# bh_ai8_di8_alph_back.net
KiCad netlist of a schematic drawn in Altium Designer
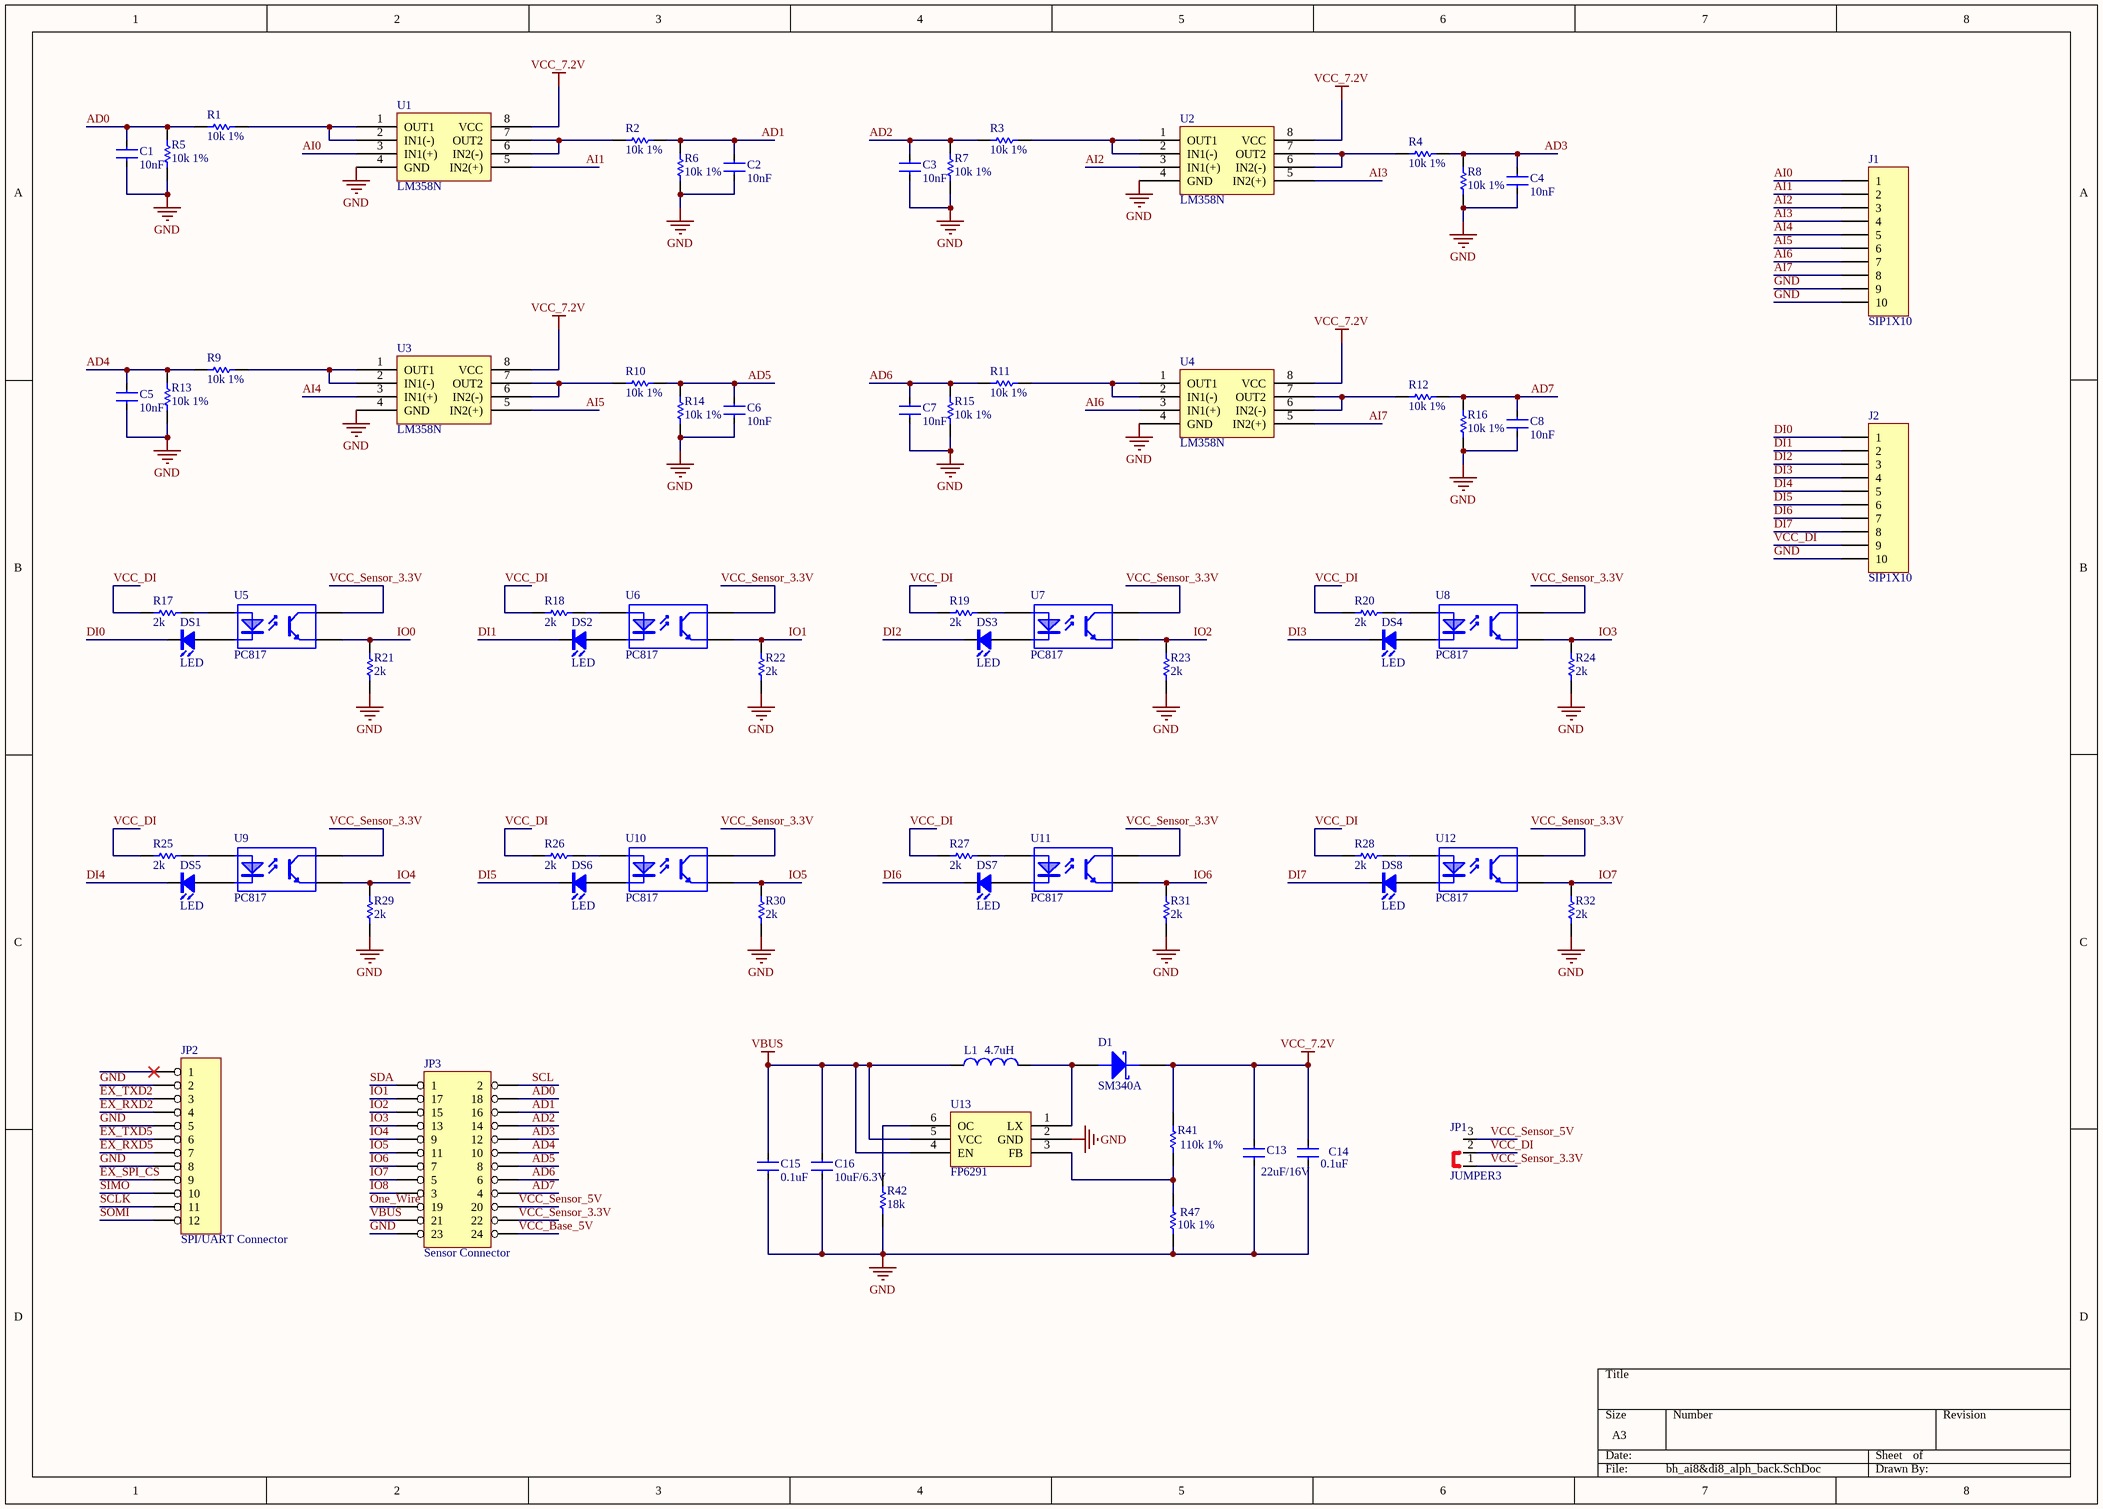
[diagram p0: bh_ai8&di8_alph_back.SchDoc]

(export (version "E")
  (design (tool "Eeschema 10.0.6"))
  (components
    (comp (ref "C1")
      (value "10nF")
      (footprint "C0603")
      (description "SMD-CAP")
      (fields (field (name "Comment") "CAP-SMD"))
      (libsource (lib "BH_DESIGN_DEVICE") (part "CAP-SMD"))
    )
    (comp (ref "C2")
      (value "10nF")
      (footprint "C0603")
      (description "SMD-CAP")
      (fields (field (name "Comment") "CAP-SMD"))
      (libsource (lib "BH_DESIGN_DEVICE") (part "CAP-SMD"))
    )
    (comp (ref "C3")
      (value "10nF")
      (footprint "C0603")
      (description "SMD-CAP")
      (fields (field (name "Comment") "CAP-SMD"))
      (libsource (lib "BH_DESIGN_DEVICE") (part "CAP-SMD"))
    )
    (comp (ref "C4")
      (value "10nF")
      (footprint "C0603")
      (description "SMD-CAP")
      (fields (field (name "Comment") "CAP-SMD"))
      (libsource (lib "BH_DESIGN_DEVICE") (part "CAP-SMD"))
    )
    (comp (ref "C5")
      (value "10nF")
      (footprint "C0603")
      (description "SMD-CAP")
      (fields (field (name "Comment") "CAP-SMD"))
      (libsource (lib "BH_DESIGN_DEVICE") (part "CAP-SMD"))
    )
    (comp (ref "C6")
      (value "10nF")
      (footprint "C0603")
      (description "SMD-CAP")
      (fields (field (name "Comment") "CAP-SMD"))
      (libsource (lib "BH_DESIGN_DEVICE") (part "CAP-SMD"))
    )
    (comp (ref "C7")
      (value "10nF")
      (footprint "C0603")
      (description "SMD-CAP")
      (fields (field (name "Comment") "CAP-SMD"))
      (libsource (lib "BH_DESIGN_DEVICE") (part "CAP-SMD"))
    )
    (comp (ref "C8")
      (value "10nF")
      (footprint "C0603")
      (description "SMD-CAP")
      (fields (field (name "Comment") "CAP-SMD"))
      (libsource (lib "BH_DESIGN_DEVICE") (part "CAP-SMD"))
    )
    (comp (ref "C13")
      (value "22uF/16V")
      (footprint "C0805")
      (description "SMD-CAP")
      (libsource (lib "5D_DEVICE") (part "CAP-SMD"))
    )
    (comp (ref "C14")
      (value "0.1uF")
      (footprint "C0603")
      (description "SMD-CAP")
      (libsource (lib "5D_DEVICE") (part "CAP-SMD"))
    )
    (comp (ref "C15")
      (value "0.1uF")
      (footprint "C0603")
      (description "SMD-CAP")
      (libsource (lib "5D_DEVICE") (part "CAP-SMD"))
    )
    (comp (ref "C16")
      (value "10uF/6.3V")
      (footprint "C0805")
      (description "SMD-CAP")
      (libsource (lib "5D_DEVICE") (part "CAP-SMD"))
    )
    (comp (ref "D1")
      (value "SM340A")
      (footprint "DO-214")
      (description "Schottky Diode")
      (libsource (lib "5D_DEVICE") (part "DIODE SCHOTTKY"))
    )
    (comp (ref "DS1") (value "LED") (footprint "D0805") (libsource (lib "BH_DESIGN_DEVICE") (part "LED")))
    (comp (ref "DS2") (value "LED") (footprint "D0805") (libsource (lib "BH_DESIGN_DEVICE") (part "LED")))
    (comp (ref "DS3") (value "LED") (footprint "D0805") (libsource (lib "BH_DESIGN_DEVICE") (part "LED")))
    (comp (ref "DS4") (value "LED") (footprint "D0805") (libsource (lib "BH_DESIGN_DEVICE") (part "LED")))
    (comp (ref "DS5") (value "LED") (footprint "D0805") (libsource (lib "BH_DESIGN_DEVICE") (part "LED")))
    (comp (ref "DS6") (value "LED") (footprint "D0805") (libsource (lib "BH_DESIGN_DEVICE") (part "LED")))
    (comp (ref "DS7") (value "LED") (footprint "D0805") (libsource (lib "BH_DESIGN_DEVICE") (part "LED")))
    (comp (ref "DS8") (value "LED") (footprint "D0805") (libsource (lib "BH_DESIGN_DEVICE") (part "LED")))
    (comp (ref "J1")
      (value "SIP1X10")
      (footprint "CON10*0.381")
      (description "Connector")
      (libsource (lib "BH_DESIGN_CONNECTOR") (part "SIP1X10"))
    )
    (comp (ref "J2")
      (value "SIP1X10")
      (footprint "CON10*0.381")
      (description "Connector")
      (libsource (lib "BH_DESIGN_CONNECTOR") (part "SIP1X10"))
    )
    (comp (ref "JP1")
      (value "JUMPER3")
      (footprint "SIP1X3X2.54")
      (description "Jumper")
      (libsource (lib "BH_DESIGN_CONNECTOR") (part "JUMPER3"))
    )
    (comp (ref "JP2")
      (value "SPI/UART Connector")
      (footprint "SIP1x12x2.54")
      (description "12 Pin Header")
      (libsource (lib "5D_CONNECTOR") (part "SIP1X12"))
    )
    (comp (ref "JP3")
      (value "Sensor Connector")
      (footprint "SIP2X12X2.54")
      (libsource (lib "5D_CONNECTOR") (part "SIP2X12"))
    )
    (comp (ref "L1")
      (value "4.7uH")
      (footprint "R1206")
      (description "Inductor")
      (fields (field (name "Comment") "INDUCTOR"))
      (libsource (lib "5D_DEVICE") (part "INDUCTOR"))
    )
    (comp (ref "R1")
      (value "10k 1%")
      (footprint "R0603")
      (description "Resistor")
      (libsource (lib "BH_DESIGN_DEVICE") (part "RES"))
    )
    (comp (ref "R2")
      (value "10k 1%")
      (footprint "R0603")
      (description "Resistor")
      (libsource (lib "BH_DESIGN_DEVICE") (part "RES"))
    )
    (comp (ref "R3")
      (value "10k 1%")
      (footprint "R0603")
      (description "Resistor")
      (libsource (lib "BH_DESIGN_DEVICE") (part "RES"))
    )
    (comp (ref "R4")
      (value "10k 1%")
      (footprint "R0603")
      (description "Resistor")
      (libsource (lib "BH_DESIGN_DEVICE") (part "RES"))
    )
    (comp (ref "R5")
      (value "10k 1%")
      (footprint "R0603")
      (description "Resistor")
      (libsource (lib "BH_DESIGN_DEVICE") (part "RES"))
    )
    (comp (ref "R6")
      (value "10k 1%")
      (footprint "R0603")
      (description "Resistor")
      (libsource (lib "BH_DESIGN_DEVICE") (part "RES"))
    )
    (comp (ref "R7")
      (value "10k 1%")
      (footprint "R0603")
      (description "Resistor")
      (libsource (lib "BH_DESIGN_DEVICE") (part "RES"))
    )
    (comp (ref "R8")
      (value "10k 1%")
      (footprint "R0603")
      (description "Resistor")
      (libsource (lib "BH_DESIGN_DEVICE") (part "RES"))
    )
    (comp (ref "R9")
      (value "10k 1%")
      (footprint "R0603")
      (description "Resistor")
      (libsource (lib "BH_DESIGN_DEVICE") (part "RES"))
    )
    (comp (ref "R10")
      (value "10k 1%")
      (footprint "R0603")
      (description "Resistor")
      (libsource (lib "BH_DESIGN_DEVICE") (part "RES"))
    )
    (comp (ref "R11")
      (value "10k 1%")
      (footprint "R0603")
      (description "Resistor")
      (libsource (lib "BH_DESIGN_DEVICE") (part "RES"))
    )
    (comp (ref "R12")
      (value "10k 1%")
      (footprint "R0603")
      (description "Resistor")
      (libsource (lib "BH_DESIGN_DEVICE") (part "RES"))
    )
    (comp (ref "R13")
      (value "10k 1%")
      (footprint "R0603")
      (description "Resistor")
      (libsource (lib "BH_DESIGN_DEVICE") (part "RES"))
    )
    (comp (ref "R14")
      (value "10k 1%")
      (footprint "R0603")
      (description "Resistor")
      (libsource (lib "BH_DESIGN_DEVICE") (part "RES"))
    )
    (comp (ref "R15")
      (value "10k 1%")
      (footprint "R0603")
      (description "Resistor")
      (libsource (lib "BH_DESIGN_DEVICE") (part "RES"))
    )
    (comp (ref "R16")
      (value "10k 1%")
      (footprint "R0603")
      (description "Resistor")
      (libsource (lib "BH_DESIGN_DEVICE") (part "RES"))
    )
    (comp (ref "R17")
      (value "2k")
      (footprint "R0603")
      (description "Resistor")
      (libsource (lib "BH_DESIGN_DEVICE") (part "RES"))
    )
    (comp (ref "R18")
      (value "2k")
      (footprint "R0603")
      (description "Resistor")
      (libsource (lib "BH_DESIGN_DEVICE") (part "RES"))
    )
    (comp (ref "R19")
      (value "2k")
      (footprint "R0603")
      (description "Resistor")
      (libsource (lib "BH_DESIGN_DEVICE") (part "RES"))
    )
    (comp (ref "R20")
      (value "2k")
      (footprint "R0603")
      (description "Resistor")
      (libsource (lib "BH_DESIGN_DEVICE") (part "RES"))
    )
    (comp (ref "R21")
      (value "2k")
      (footprint "R0603")
      (description "Resistor")
      (libsource (lib "BH_DESIGN_DEVICE") (part "RES"))
    )
    (comp (ref "R22")
      (value "2k")
      (footprint "R0603")
      (description "Resistor")
      (libsource (lib "BH_DESIGN_DEVICE") (part "RES"))
    )
    (comp (ref "R23")
      (value "2k")
      (footprint "R0603")
      (description "Resistor")
      (libsource (lib "BH_DESIGN_DEVICE") (part "RES"))
    )
    (comp (ref "R24")
      (value "2k")
      (footprint "R0603")
      (description "Resistor")
      (libsource (lib "BH_DESIGN_DEVICE") (part "RES"))
    )
    (comp (ref "R25")
      (value "2k")
      (footprint "R0603")
      (description "Resistor")
      (libsource (lib "BH_DESIGN_DEVICE") (part "RES"))
    )
    (comp (ref "R26")
      (value "2k")
      (footprint "R0603")
      (description "Resistor")
      (libsource (lib "BH_DESIGN_DEVICE") (part "RES"))
    )
    (comp (ref "R27")
      (value "2k")
      (footprint "R0603")
      (description "Resistor")
      (libsource (lib "BH_DESIGN_DEVICE") (part "RES"))
    )
    (comp (ref "R28")
      (value "2k")
      (footprint "R0603")
      (description "Resistor")
      (libsource (lib "BH_DESIGN_DEVICE") (part "RES"))
    )
    (comp (ref "R29")
      (value "2k")
      (footprint "R0603")
      (description "Resistor")
      (libsource (lib "BH_DESIGN_DEVICE") (part "RES"))
    )
    (comp (ref "R30")
      (value "2k")
      (footprint "R0603")
      (description "Resistor")
      (libsource (lib "BH_DESIGN_DEVICE") (part "RES"))
    )
    (comp (ref "R31")
      (value "2k")
      (footprint "R0603")
      (description "Resistor")
      (libsource (lib "BH_DESIGN_DEVICE") (part "RES"))
    )
    (comp (ref "R32")
      (value "2k")
      (footprint "R0603")
      (description "Resistor")
      (libsource (lib "BH_DESIGN_DEVICE") (part "RES"))
    )
    (comp (ref "R41")
      (value "110k 1%")
      (footprint "R0603")
      (description "Resistor")
      (libsource (lib "5D_DEVICE") (part "RES"))
    )
    (comp (ref "R42")
      (value "18k")
      (footprint "R0603")
      (description "Resistor")
      (libsource (lib "5D_DEVICE") (part "RES"))
    )
    (comp (ref "R47")
      (value "10k 1%")
      (footprint "R0603")
      (description "Resistor")
      (libsource (lib "5D_DEVICE") (part "RES"))
    )
    (comp (ref "U1") (value "LM358N") (footprint "SO8NB") (libsource (lib "BH_DESIGN_IC") (part "LM358N")))
    (comp (ref "U2") (value "LM358N") (footprint "SO8NB") (libsource (lib "BH_DESIGN_IC") (part "LM358N")))
    (comp (ref "U3") (value "LM358N") (footprint "SO8NB") (libsource (lib "BH_DESIGN_IC") (part "LM358N")))
    (comp (ref "U4") (value "LM358N") (footprint "SO8NB") (libsource (lib "BH_DESIGN_IC") (part "LM358N")))
    (comp (ref "U5")
      (value "PC817")
      (footprint "SOP_4")
      (fields (field (name "PUBLISHER") "Altium Limited"))
      (libsource (lib "BH_DESIGN_DEVICE") (part "P521*1"))
    )
    (comp (ref "U6")
      (value "PC817")
      (footprint "SOP_4")
      (fields (field (name "PUBLISHER") "Altium Limited"))
      (libsource (lib "BH_DESIGN_DEVICE") (part "P521*1"))
    )
    (comp (ref "U7")
      (value "PC817")
      (footprint "SOP_4")
      (fields (field (name "PUBLISHER") "Altium Limited"))
      (libsource (lib "BH_DESIGN_DEVICE") (part "P521*1"))
    )
    (comp (ref "U8")
      (value "PC817")
      (footprint "SOP_4")
      (fields (field (name "PUBLISHER") "Altium Limited"))
      (libsource (lib "BH_DESIGN_DEVICE") (part "P521*1"))
    )
    (comp (ref "U9")
      (value "PC817")
      (footprint "SOP_4")
      (fields (field (name "PUBLISHER") "Altium Limited"))
      (libsource (lib "BH_DESIGN_DEVICE") (part "P521*1"))
    )
    (comp (ref "U10")
      (value "PC817")
      (footprint "SOP_4")
      (fields (field (name "PUBLISHER") "Altium Limited"))
      (libsource (lib "BH_DESIGN_DEVICE") (part "P521*1"))
    )
    (comp (ref "U11")
      (value "PC817")
      (footprint "SOP_4")
      (fields (field (name "PUBLISHER") "Altium Limited"))
      (libsource (lib "BH_DESIGN_DEVICE") (part "P521*1"))
    )
    (comp (ref "U12")
      (value "PC817")
      (footprint "SOP_4")
      (fields (field (name "PUBLISHER") "Altium Limited"))
      (libsource (lib "BH_DESIGN_DEVICE") (part "P521*1"))
    )
    (comp (ref "U13") (value "FP6291") (footprint "SOT23-6") (libsource (lib "5D_IC") (part "FP6291")))
  )
  (nets
    (net (code "1") (name "/AD0") (class "Default")
      (node (ref "C1") (pin "1") (pinfunction "1_1") (pintype "passive"))
      (node (ref "JP3") (pin "18") (pinfunction "18_18") (pintype "passive"))
      (node (ref "R1") (pin "2") (pinfunction "2_2") (pintype "passive"))
      (node (ref "R5") (pin "1") (pinfunction "1_1") (pintype "passive"))
    )
    (net (code "2") (name "/AD1") (class "Default")
      (node (ref "C2") (pin "1") (pinfunction "1_1") (pintype "passive"))
      (node (ref "JP3") (pin "16") (pinfunction "16_16") (pintype "passive"))
      (node (ref "R2") (pin "1") (pinfunction "1_1") (pintype "passive"))
      (node (ref "R6") (pin "1") (pinfunction "1_1") (pintype "passive"))
    )
    (net (code "3") (name "/AD2") (class "Default")
      (node (ref "C3") (pin "1") (pinfunction "1_1") (pintype "passive"))
      (node (ref "JP3") (pin "14") (pinfunction "14_14") (pintype "passive"))
      (node (ref "R3") (pin "2") (pinfunction "2_2") (pintype "passive"))
      (node (ref "R7") (pin "1") (pinfunction "1_1") (pintype "passive"))
    )
    (net (code "4") (name "/AD3") (class "Default")
      (node (ref "C4") (pin "1") (pinfunction "1_1") (pintype "passive"))
      (node (ref "JP3") (pin "12") (pinfunction "12_12") (pintype "passive"))
      (node (ref "R4") (pin "1") (pinfunction "1_1") (pintype "passive"))
      (node (ref "R8") (pin "1") (pinfunction "1_1") (pintype "passive"))
    )
    (net (code "5") (name "/AD4") (class "Default")
      (node (ref "C5") (pin "1") (pinfunction "1_1") (pintype "passive"))
      (node (ref "JP3") (pin "10") (pinfunction "10_10") (pintype "passive"))
      (node (ref "R13") (pin "1") (pinfunction "1_1") (pintype "passive"))
      (node (ref "R9") (pin "2") (pinfunction "2_2") (pintype "passive"))
    )
    (net (code "6") (name "/AD5") (class "Default")
      (node (ref "C6") (pin "1") (pinfunction "1_1") (pintype "passive"))
      (node (ref "JP3") (pin "8") (pinfunction "8_8") (pintype "passive"))
      (node (ref "R10") (pin "1") (pinfunction "1_1") (pintype "passive"))
      (node (ref "R14") (pin "1") (pinfunction "1_1") (pintype "passive"))
    )
    (net (code "7") (name "/AD6") (class "Default")
      (node (ref "C7") (pin "1") (pinfunction "1_1") (pintype "passive"))
      (node (ref "JP3") (pin "6") (pinfunction "6_6") (pintype "passive"))
      (node (ref "R11") (pin "2") (pinfunction "2_2") (pintype "passive"))
      (node (ref "R15") (pin "1") (pinfunction "1_1") (pintype "passive"))
    )
    (net (code "8") (name "/AD7") (class "Default")
      (node (ref "C8") (pin "1") (pinfunction "1_1") (pintype "passive"))
      (node (ref "JP3") (pin "4") (pinfunction "4_4") (pintype "passive"))
      (node (ref "R12") (pin "1") (pinfunction "1_1") (pintype "passive"))
      (node (ref "R16") (pin "1") (pinfunction "1_1") (pintype "passive"))
    )
    (net (code "9") (name "/AI0") (class "Default")
      (node (ref "J1") (pin "1") (pinfunction "1_1") (pintype "passive"))
      (node (ref "U1") (pin "3") (pinfunction "IN1(+)_3") (pintype "passive"))
    )
    (net (code "10") (name "/AI1") (class "Default")
      (node (ref "J1") (pin "2") (pinfunction "2_2") (pintype "passive"))
      (node (ref "U1") (pin "5") (pinfunction "IN2(+)_5") (pintype "passive"))
    )
    (net (code "11") (name "/AI2") (class "Default")
      (node (ref "J1") (pin "3") (pinfunction "3_3") (pintype "passive"))
      (node (ref "U2") (pin "3") (pinfunction "IN1(+)_3") (pintype "passive"))
    )
    (net (code "12") (name "/AI3") (class "Default")
      (node (ref "J1") (pin "4") (pinfunction "4_4") (pintype "passive"))
      (node (ref "U2") (pin "5") (pinfunction "IN2(+)_5") (pintype "passive"))
    )
    (net (code "13") (name "/AI4") (class "Default")
      (node (ref "J1") (pin "5") (pinfunction "5_5") (pintype "passive"))
      (node (ref "U3") (pin "3") (pinfunction "IN1(+)_3") (pintype "passive"))
    )
    (net (code "14") (name "/AI5") (class "Default")
      (node (ref "J1") (pin "6") (pinfunction "6_6") (pintype "passive"))
      (node (ref "U3") (pin "5") (pinfunction "IN2(+)_5") (pintype "passive"))
    )
    (net (code "15") (name "/AI6") (class "Default")
      (node (ref "J1") (pin "7") (pinfunction "7_7") (pintype "passive"))
      (node (ref "U4") (pin "3") (pinfunction "IN1(+)_3") (pintype "passive"))
    )
    (net (code "16") (name "/AI7") (class "Default")
      (node (ref "J1") (pin "8") (pinfunction "8_8") (pintype "passive"))
      (node (ref "U4") (pin "5") (pinfunction "IN2(+)_5") (pintype "passive"))
    )
    (net (code "17") (name "/DI0") (class "Default")
      (node (ref "DS1") (pin "K") (pinfunction "2_K") (pintype "passive"))
      (node (ref "J2") (pin "1") (pinfunction "1_1") (pintype "passive"))
    )
    (net (code "18") (name "/DI1") (class "Default")
      (node (ref "DS2") (pin "K") (pinfunction "2_K") (pintype "passive"))
      (node (ref "J2") (pin "2") (pinfunction "2_2") (pintype "passive"))
    )
    (net (code "19") (name "/DI2") (class "Default")
      (node (ref "DS3") (pin "K") (pinfunction "2_K") (pintype "passive"))
      (node (ref "J2") (pin "3") (pinfunction "3_3") (pintype "passive"))
    )
    (net (code "20") (name "/DI3") (class "Default")
      (node (ref "DS4") (pin "K") (pinfunction "2_K") (pintype "passive"))
      (node (ref "J2") (pin "4") (pinfunction "4_4") (pintype "passive"))
    )
    (net (code "21") (name "/DI4") (class "Default")
      (node (ref "DS5") (pin "K") (pinfunction "2_K") (pintype "passive"))
      (node (ref "J2") (pin "5") (pinfunction "5_5") (pintype "passive"))
    )
    (net (code "22") (name "/DI5") (class "Default")
      (node (ref "DS6") (pin "K") (pinfunction "2_K") (pintype "passive"))
      (node (ref "J2") (pin "6") (pinfunction "6_6") (pintype "passive"))
    )
    (net (code "23") (name "/DI6") (class "Default")
      (node (ref "DS7") (pin "K") (pinfunction "2_K") (pintype "passive"))
      (node (ref "J2") (pin "7") (pinfunction "7_7") (pintype "passive"))
    )
    (net (code "24") (name "/DI7") (class "Default")
      (node (ref "DS8") (pin "K") (pinfunction "2_K") (pintype "passive"))
      (node (ref "J2") (pin "8") (pinfunction "8_8") (pintype "passive"))
    )
    (net (code "25") (name "/EX_RXD2") (class "Default")
      (node (ref "JP2") (pin "4") (pinfunction "4_4") (pintype "passive"))
    )
    (net (code "26") (name "/EX_RXD5") (class "Default")
      (node (ref "JP2") (pin "7") (pinfunction "7_7") (pintype "passive"))
    )
    (net (code "27") (name "/EX_SPI_CS") (class "Default")
      (node (ref "JP2") (pin "9") (pinfunction "9_9") (pintype "passive"))
    )
    (net (code "28") (name "/EX_TXD2") (class "Default")
      (node (ref "JP2") (pin "3") (pinfunction "3_3") (pintype "passive"))
    )
    (net (code "29") (name "/EX_TXD5") (class "Default")
      (node (ref "JP2") (pin "6") (pinfunction "6_6") (pintype "passive"))
    )
    (net (code "30") (name "/IO0") (class "Default")
      (node (ref "R21") (pin "1") (pinfunction "1_1") (pintype "passive"))
      (node (ref "U5") (pin "3") (pinfunction "E_3") (pintype "passive"))
    )
    (net (code "31") (name "/IO1") (class "Default")
      (node (ref "JP3") (pin "17") (pinfunction "17_17") (pintype "passive"))
      (node (ref "R22") (pin "1") (pinfunction "1_1") (pintype "passive"))
      (node (ref "U6") (pin "3") (pinfunction "E_3") (pintype "passive"))
    )
    (net (code "32") (name "/IO2") (class "Default")
      (node (ref "JP3") (pin "15") (pinfunction "15_15") (pintype "passive"))
      (node (ref "R23") (pin "1") (pinfunction "1_1") (pintype "passive"))
      (node (ref "U7") (pin "3") (pinfunction "E_3") (pintype "passive"))
    )
    (net (code "33") (name "/IO3") (class "Default")
      (node (ref "JP3") (pin "13") (pinfunction "13_13") (pintype "passive"))
      (node (ref "R24") (pin "1") (pinfunction "1_1") (pintype "passive"))
      (node (ref "U8") (pin "3") (pinfunction "E_3") (pintype "passive"))
    )
    (net (code "34") (name "/IO4") (class "Default")
      (node (ref "JP3") (pin "9") (pinfunction "9_9") (pintype "passive"))
      (node (ref "R29") (pin "1") (pinfunction "1_1") (pintype "passive"))
      (node (ref "U9") (pin "3") (pinfunction "E_3") (pintype "passive"))
    )
    (net (code "35") (name "/IO5") (class "Default")
      (node (ref "JP3") (pin "11") (pinfunction "11_11") (pintype "passive"))
      (node (ref "R30") (pin "1") (pinfunction "1_1") (pintype "passive"))
      (node (ref "U10") (pin "3") (pinfunction "E_3") (pintype "passive"))
    )
    (net (code "36") (name "/IO6") (class "Default")
      (node (ref "JP3") (pin "7") (pinfunction "7_7") (pintype "passive"))
      (node (ref "R31") (pin "1") (pinfunction "1_1") (pintype "passive"))
      (node (ref "U11") (pin "3") (pinfunction "E_3") (pintype "passive"))
    )
    (net (code "37") (name "/IO7") (class "Default")
      (node (ref "JP3") (pin "5") (pinfunction "5_5") (pintype "passive"))
      (node (ref "R32") (pin "1") (pinfunction "1_1") (pintype "passive"))
      (node (ref "U12") (pin "3") (pinfunction "E_3") (pintype "passive"))
    )
    (net (code "38") (name "/IO8") (class "Default")
      (node (ref "JP3") (pin "3") (pinfunction "3_3") (pintype "passive"))
    )
    (net (code "39") (name "/One_Wire") (class "Default")
      (node (ref "JP3") (pin "19") (pinfunction "19_19") (pintype "passive"))
    )
    (net (code "40") (name "/SCL") (class "Default")
      (node (ref "JP3") (pin "2") (pinfunction "2_2") (pintype "passive"))
    )
    (net (code "41") (name "/SCLK") (class "Default")
      (node (ref "JP2") (pin "11") (pinfunction "11_11") (pintype "passive"))
    )
    (net (code "42") (name "/SDA") (class "Default")
      (node (ref "JP3") (pin "1") (pinfunction "1_1") (pintype "passive"))
    )
    (net (code "43") (name "/SIMO") (class "Default")
      (node (ref "JP2") (pin "10") (pinfunction "10_10") (pintype "passive"))
    )
    (net (code "44") (name "/SOMI") (class "Default")
      (node (ref "JP2") (pin "12") (pinfunction "12_12") (pintype "passive"))
    )
    (net (code "45") (name "/VCC_Base_5V") (class "Default")
      (node (ref "JP3") (pin "24") (pinfunction "24_24") (pintype "passive"))
    )
    (net (code "46") (name "/VCC_DI") (class "Default")
      (node (ref "J2") (pin "9") (pinfunction "9_9") (pintype "passive"))
      (node (ref "JP1") (pin "2") (pinfunction "2_2") (pintype "passive"))
      (node (ref "R17") (pin "2") (pinfunction "2_2") (pintype "passive"))
      (node (ref "R18") (pin "2") (pinfunction "2_2") (pintype "passive"))
      (node (ref "R19") (pin "2") (pinfunction "2_2") (pintype "passive"))
      (node (ref "R20") (pin "2") (pinfunction "2_2") (pintype "passive"))
      (node (ref "R25") (pin "2") (pinfunction "2_2") (pintype "passive"))
      (node (ref "R26") (pin "2") (pinfunction "2_2") (pintype "passive"))
      (node (ref "R27") (pin "2") (pinfunction "2_2") (pintype "passive"))
      (node (ref "R28") (pin "2") (pinfunction "2_2") (pintype "passive"))
    )
    (net (code "47") (name "/VCC_Sensor_3.3V") (class "Default")
      (node (ref "JP1") (pin "1") (pinfunction "1_1") (pintype "passive"))
      (node (ref "JP3") (pin "22") (pinfunction "22_22") (pintype "passive"))
      (node (ref "U10") (pin "4") (pinfunction "C_4") (pintype "passive"))
      (node (ref "U11") (pin "4") (pinfunction "C_4") (pintype "passive"))
      (node (ref "U12") (pin "4") (pinfunction "C_4") (pintype "passive"))
      (node (ref "U5") (pin "4") (pinfunction "C_4") (pintype "passive"))
      (node (ref "U6") (pin "4") (pinfunction "C_4") (pintype "passive"))
      (node (ref "U7") (pin "4") (pinfunction "C_4") (pintype "passive"))
      (node (ref "U8") (pin "4") (pinfunction "C_4") (pintype "passive"))
      (node (ref "U9") (pin "4") (pinfunction "C_4") (pintype "passive"))
    )
    (net (code "48") (name "/VCC_Sensor_5V") (class "Default")
      (node (ref "JP1") (pin "3") (pinfunction "3_3") (pintype "passive"))
      (node (ref "JP3") (pin "20") (pinfunction "20_20") (pintype "passive"))
    )
    (net (code "49") (name "GND") (class "Default")
      (node (ref "C1") (pin "2") (pinfunction "2_2") (pintype "passive"))
      (node (ref "C13") (pin "2") (pinfunction "2_2") (pintype "passive"))
      (node (ref "C14") (pin "2") (pinfunction "2_2") (pintype "passive"))
      (node (ref "C15") (pin "2") (pinfunction "2_2") (pintype "passive"))
      (node (ref "C16") (pin "2") (pinfunction "2_2") (pintype "passive"))
      (node (ref "C2") (pin "2") (pinfunction "2_2") (pintype "passive"))
      (node (ref "C3") (pin "2") (pinfunction "2_2") (pintype "passive"))
      (node (ref "C4") (pin "2") (pinfunction "2_2") (pintype "passive"))
      (node (ref "C5") (pin "2") (pinfunction "2_2") (pintype "passive"))
      (node (ref "C6") (pin "2") (pinfunction "2_2") (pintype "passive"))
      (node (ref "C7") (pin "2") (pinfunction "2_2") (pintype "passive"))
      (node (ref "C8") (pin "2") (pinfunction "2_2") (pintype "passive"))
      (node (ref "J1") (pin "10") (pinfunction "10_10") (pintype "passive"))
      (node (ref "J1") (pin "9") (pinfunction "9_9") (pintype "passive"))
      (node (ref "J2") (pin "10") (pinfunction "10_10") (pintype "passive"))
      (node (ref "JP2") (pin "2") (pinfunction "2_2") (pintype "passive"))
      (node (ref "JP2") (pin "5") (pinfunction "5_5") (pintype "passive"))
      (node (ref "JP2") (pin "8") (pinfunction "8_8") (pintype "passive"))
      (node (ref "JP3") (pin "23") (pinfunction "23_23") (pintype "passive"))
      (node (ref "R13") (pin "2") (pinfunction "2_2") (pintype "passive"))
      (node (ref "R14") (pin "2") (pinfunction "2_2") (pintype "passive"))
      (node (ref "R15") (pin "2") (pinfunction "2_2") (pintype "passive"))
      (node (ref "R16") (pin "2") (pinfunction "2_2") (pintype "passive"))
      (node (ref "R21") (pin "2") (pinfunction "2_2") (pintype "passive"))
      (node (ref "R22") (pin "2") (pinfunction "2_2") (pintype "passive"))
      (node (ref "R23") (pin "2") (pinfunction "2_2") (pintype "passive"))
      (node (ref "R24") (pin "2") (pinfunction "2_2") (pintype "passive"))
      (node (ref "R29") (pin "2") (pinfunction "2_2") (pintype "passive"))
      (node (ref "R30") (pin "2") (pinfunction "2_2") (pintype "passive"))
      (node (ref "R31") (pin "2") (pinfunction "2_2") (pintype "passive"))
      (node (ref "R32") (pin "2") (pinfunction "2_2") (pintype "passive"))
      (node (ref "R42") (pin "1") (pinfunction "1_1") (pintype "passive"))
      (node (ref "R47") (pin "1") (pinfunction "1_1") (pintype "passive"))
      (node (ref "R5") (pin "2") (pinfunction "2_2") (pintype "passive"))
      (node (ref "R6") (pin "2") (pinfunction "2_2") (pintype "passive"))
      (node (ref "R7") (pin "2") (pinfunction "2_2") (pintype "passive"))
      (node (ref "R8") (pin "2") (pinfunction "2_2") (pintype "passive"))
      (node (ref "U1") (pin "4") (pinfunction "GND_4") (pintype "passive"))
      (node (ref "U13") (pin "2") (pinfunction "GND_2") (pintype "passive"))
      (node (ref "U2") (pin "4") (pinfunction "GND_4") (pintype "passive"))
      (node (ref "U3") (pin "4") (pinfunction "GND_4") (pintype "passive"))
      (node (ref "U4") (pin "4") (pinfunction "GND_4") (pintype "passive"))
    )
    (net (code "50") (name "Net-(D1-A)") (class "Default")
      (node (ref "D1") (pin "1") (pinfunction "A_1") (pintype "passive"))
      (node (ref "L1") (pin "2") (pinfunction "2_2") (pintype "passive"))
      (node (ref "U13") (pin "1") (pinfunction "LX_1") (pintype "passive"))
    )
    (net (code "51") (name "Net-(DS1-1)") (class "Default")
      (node (ref "DS1") (pin "A") (pinfunction "1_A") (pintype "passive"))
      (node (ref "U5") (pin "2") (pinfunction "K_2") (pintype "passive"))
    )
    (net (code "52") (name "Net-(DS2-1)") (class "Default")
      (node (ref "DS2") (pin "A") (pinfunction "1_A") (pintype "passive"))
      (node (ref "U6") (pin "2") (pinfunction "K_2") (pintype "passive"))
    )
    (net (code "53") (name "Net-(DS3-1)") (class "Default")
      (node (ref "DS3") (pin "A") (pinfunction "1_A") (pintype "passive"))
      (node (ref "U7") (pin "2") (pinfunction "K_2") (pintype "passive"))
    )
    (net (code "54") (name "Net-(DS4-1)") (class "Default")
      (node (ref "DS4") (pin "A") (pinfunction "1_A") (pintype "passive"))
      (node (ref "U8") (pin "2") (pinfunction "K_2") (pintype "passive"))
    )
    (net (code "55") (name "Net-(DS5-1)") (class "Default")
      (node (ref "DS5") (pin "A") (pinfunction "1_A") (pintype "passive"))
      (node (ref "U9") (pin "2") (pinfunction "K_2") (pintype "passive"))
    )
    (net (code "56") (name "Net-(DS6-1)") (class "Default")
      (node (ref "DS6") (pin "A") (pinfunction "1_A") (pintype "passive"))
      (node (ref "U10") (pin "2") (pinfunction "K_2") (pintype "passive"))
    )
    (net (code "57") (name "Net-(DS7-1)") (class "Default")
      (node (ref "DS7") (pin "A") (pinfunction "1_A") (pintype "passive"))
      (node (ref "U11") (pin "2") (pinfunction "K_2") (pintype "passive"))
    )
    (net (code "58") (name "Net-(DS8-1)") (class "Default")
      (node (ref "DS8") (pin "A") (pinfunction "1_A") (pintype "passive"))
      (node (ref "U12") (pin "2") (pinfunction "K_2") (pintype "passive"))
    )
    (net (code "59") (name "Net-(U1-IN1(-))") (class "Default")
      (node (ref "R1") (pin "1") (pinfunction "1_1") (pintype "passive"))
      (node (ref "U1") (pin "1") (pinfunction "OUT1_1") (pintype "passive"))
      (node (ref "U1") (pin "2") (pinfunction "IN1(-)_2") (pintype "passive"))
    )
    (net (code "60") (name "Net-(U1-IN2(-))") (class "Default")
      (node (ref "R2") (pin "2") (pinfunction "2_2") (pintype "passive"))
      (node (ref "U1") (pin "6") (pinfunction "IN2(-)_6") (pintype "passive"))
      (node (ref "U1") (pin "7") (pinfunction "OUT2_7") (pintype "passive"))
    )
    (net (code "61") (name "Net-(U2-IN1(-))") (class "Default")
      (node (ref "R3") (pin "1") (pinfunction "1_1") (pintype "passive"))
      (node (ref "U2") (pin "1") (pinfunction "OUT1_1") (pintype "passive"))
      (node (ref "U2") (pin "2") (pinfunction "IN1(-)_2") (pintype "passive"))
    )
    (net (code "62") (name "Net-(U2-IN2(-))") (class "Default")
      (node (ref "R4") (pin "2") (pinfunction "2_2") (pintype "passive"))
      (node (ref "U2") (pin "6") (pinfunction "IN2(-)_6") (pintype "passive"))
      (node (ref "U2") (pin "7") (pinfunction "OUT2_7") (pintype "passive"))
    )
    (net (code "63") (name "Net-(U3-IN1(-))") (class "Default")
      (node (ref "R9") (pin "1") (pinfunction "1_1") (pintype "passive"))
      (node (ref "U3") (pin "1") (pinfunction "OUT1_1") (pintype "passive"))
      (node (ref "U3") (pin "2") (pinfunction "IN1(-)_2") (pintype "passive"))
    )
    (net (code "64") (name "Net-(U3-IN2(-))") (class "Default")
      (node (ref "R10") (pin "2") (pinfunction "2_2") (pintype "passive"))
      (node (ref "U3") (pin "6") (pinfunction "IN2(-)_6") (pintype "passive"))
      (node (ref "U3") (pin "7") (pinfunction "OUT2_7") (pintype "passive"))
    )
    (net (code "65") (name "Net-(U4-IN1(-))") (class "Default")
      (node (ref "R11") (pin "1") (pinfunction "1_1") (pintype "passive"))
      (node (ref "U4") (pin "1") (pinfunction "OUT1_1") (pintype "passive"))
      (node (ref "U4") (pin "2") (pinfunction "IN1(-)_2") (pintype "passive"))
    )
    (net (code "66") (name "Net-(U4-IN2(-))") (class "Default")
      (node (ref "R12") (pin "2") (pinfunction "2_2") (pintype "passive"))
      (node (ref "U4") (pin "6") (pinfunction "IN2(-)_6") (pintype "passive"))
      (node (ref "U4") (pin "7") (pinfunction "OUT2_7") (pintype "passive"))
    )
    (net (code "67") (name "Net-(U5-A)") (class "Default")
      (node (ref "R17") (pin "1") (pinfunction "1_1") (pintype "passive"))
      (node (ref "U5") (pin "1") (pinfunction "A_1") (pintype "passive"))
    )
    (net (code "68") (name "Net-(U6-A)") (class "Default")
      (node (ref "R18") (pin "1") (pinfunction "1_1") (pintype "passive"))
      (node (ref "U6") (pin "1") (pinfunction "A_1") (pintype "passive"))
    )
    (net (code "69") (name "Net-(U7-A)") (class "Default")
      (node (ref "R19") (pin "1") (pinfunction "1_1") (pintype "passive"))
      (node (ref "U7") (pin "1") (pinfunction "A_1") (pintype "passive"))
    )
    (net (code "70") (name "Net-(U8-A)") (class "Default")
      (node (ref "R20") (pin "1") (pinfunction "1_1") (pintype "passive"))
      (node (ref "U8") (pin "1") (pinfunction "A_1") (pintype "passive"))
    )
    (net (code "71") (name "Net-(U9-A)") (class "Default")
      (node (ref "R25") (pin "1") (pinfunction "1_1") (pintype "passive"))
      (node (ref "U9") (pin "1") (pinfunction "A_1") (pintype "passive"))
    )
    (net (code "72") (name "Net-(U10-A)") (class "Default")
      (node (ref "R26") (pin "1") (pinfunction "1_1") (pintype "passive"))
      (node (ref "U10") (pin "1") (pinfunction "A_1") (pintype "passive"))
    )
    (net (code "73") (name "Net-(U11-A)") (class "Default")
      (node (ref "R27") (pin "1") (pinfunction "1_1") (pintype "passive"))
      (node (ref "U11") (pin "1") (pinfunction "A_1") (pintype "passive"))
    )
    (net (code "74") (name "Net-(U12-A)") (class "Default")
      (node (ref "R28") (pin "1") (pinfunction "1_1") (pintype "passive"))
      (node (ref "U12") (pin "1") (pinfunction "A_1") (pintype "passive"))
    )
    (net (code "75") (name "Net-(U13-FB)") (class "Default")
      (node (ref "R41") (pin "1") (pinfunction "1_1") (pintype "passive"))
      (node (ref "R47") (pin "2") (pinfunction "2_2") (pintype "passive"))
      (node (ref "U13") (pin "3") (pinfunction "FB_3") (pintype "passive"))
    )
    (net (code "76") (name "Net-(U13-OC)") (class "Default")
      (node (ref "R42") (pin "2") (pinfunction "2_2") (pintype "passive"))
      (node (ref "U13") (pin "6") (pinfunction "OC_6") (pintype "passive"))
    )
    (net (code "77") (name "VBUS") (class "Default")
      (node (ref "C15") (pin "1") (pinfunction "1_1") (pintype "passive"))
      (node (ref "C16") (pin "1") (pinfunction "1_1") (pintype "passive"))
      (node (ref "JP3") (pin "21") (pinfunction "21_21") (pintype "passive"))
      (node (ref "L1") (pin "1") (pinfunction "1_1") (pintype "passive"))
      (node (ref "U13") (pin "4") (pinfunction "EN_4") (pintype "passive"))
      (node (ref "U13") (pin "5") (pinfunction "VCC_5") (pintype "passive"))
    )
    (net (code "78") (name "VCC_7.2V") (class "Default")
      (node (ref "C13") (pin "1") (pinfunction "1_1") (pintype "passive"))
      (node (ref "C14") (pin "1") (pinfunction "1_1") (pintype "passive"))
      (node (ref "D1") (pin "2") (pinfunction "K_2") (pintype "passive"))
      (node (ref "R41") (pin "2") (pinfunction "2_2") (pintype "passive"))
      (node (ref "U1") (pin "8") (pinfunction "VCC_8") (pintype "passive"))
      (node (ref "U2") (pin "8") (pinfunction "VCC_8") (pintype "passive"))
      (node (ref "U3") (pin "8") (pinfunction "VCC_8") (pintype "passive"))
      (node (ref "U4") (pin "8") (pinfunction "VCC_8") (pintype "passive"))
    )
    (net (code "79") (name "unconnected-(JP2-Pad1)") (class "Default")
      (node (ref "JP2") (pin "1") (pinfunction "1_1") (pintype "passive+no_connect"))
    )
  )
)
